# LEDs.net
KiCad netlist of a schematic drawn in Altium Designer
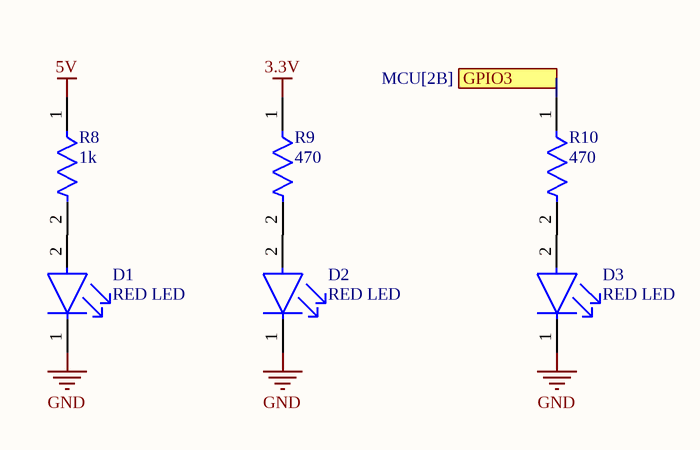
[diagram p0: LEDs.SchDoc]

(export (version "E")
  (design (tool "Eeschema 10.0.6"))
  (components
    (comp (ref "D1")
      (value "RED LED")
      (footprint "FP-APTD1608SEC-J3-MFG")
      (description "LED RED CLEAR CHIP SMD")
      (libsource (lib "Altium Content Vault") (part "8706943c75ba83719d021d2fdc84c58"))
    )
    (comp (ref "D2")
      (value "RED LED")
      (footprint "FP-APTD1608SEC-J3-MFG")
      (description "LED RED CLEAR CHIP SMD")
      (libsource (lib "Altium Content Vault") (part "8706943c75ba83719d021d2fdc84c58"))
    )
    (comp (ref "D3")
      (value "RED LED")
      (footprint "FP-APTD1608SEC-J3-MFG")
      (description "LED RED CLEAR CHIP SMD")
      (libsource (lib "Altium Content Vault") (part "8706943c75ba83719d021d2fdc84c58"))
    )
    (comp (ref "R8")
      (value "1k")
      (footprint "FP-RNCP0603-IPC_C")
      (description "1kΩ ±1% 0.125W 0603 High Power Anti-Sulfur Thin Film Chip Resistor")
      (fields (field (name "TOLERANCE") "1%"))
      (libsource (lib "Altium Content Vault") (part "1029c3af85768c4190bb7ad29bc67b5"))
    )
    (comp (ref "R9")
      (value "470")
      (footprint "FP-AC0603-IPC_A")
      (description "RES 470Ω 1.00% 0.1W 0603")
      (fields (field (name "TOLERANCE") "1%"))
      (libsource (lib "Altium Content Vault") (part "1029c3af85768c4190bb7ad29bc67b5"))
    )
    (comp (ref "R10")
      (value "470")
      (footprint "FP-AC0603-IPC_A")
      (description "RES 470Ω 1.00% 0.1W 0603")
      (fields (field (name "TOLERANCE") "1%"))
      (libsource (lib "Altium Content Vault") (part "1029c3af85768c4190bb7ad29bc67b5"))
    )
  )
  (nets
    (net (code "1") (name "/GPIO3") (class "Default")
      (node (ref "R10") (pin "1") (pinfunction "1_1") (pintype "passive"))
    )
    (net (code "2") (name "3.3V") (class "Default")
      (node (ref "R9") (pin "1") (pinfunction "1_1") (pintype "passive"))
    )
    (net (code "3") (name "5V") (class "Default")
      (node (ref "R8") (pin "1") (pinfunction "1_1") (pintype "passive"))
    )
    (net (code "4") (name "GND") (class "Default")
      (node (ref "D1") (pin "1") (pinfunction "C_1") (pintype "passive"))
      (node (ref "D2") (pin "1") (pinfunction "C_1") (pintype "passive"))
      (node (ref "D3") (pin "1") (pinfunction "C_1") (pintype "passive"))
    )
    (net (code "5") (name "Net-(D1-A)") (class "Default")
      (node (ref "D1") (pin "2") (pinfunction "A_2") (pintype "passive"))
      (node (ref "R8") (pin "2") (pinfunction "2_2") (pintype "passive"))
    )
    (net (code "6") (name "Net-(D2-A)") (class "Default")
      (node (ref "D2") (pin "2") (pinfunction "A_2") (pintype "passive"))
      (node (ref "R9") (pin "2") (pinfunction "2_2") (pintype "passive"))
    )
    (net (code "7") (name "Net-(D3-A)") (class "Default")
      (node (ref "D3") (pin "2") (pinfunction "A_2") (pintype "passive"))
      (node (ref "R10") (pin "2") (pinfunction "2_2") (pintype "passive"))
    )
  )
)
